# rf24_nano-shield.net
KiCad netlist of a schematic drawn in EAGLE
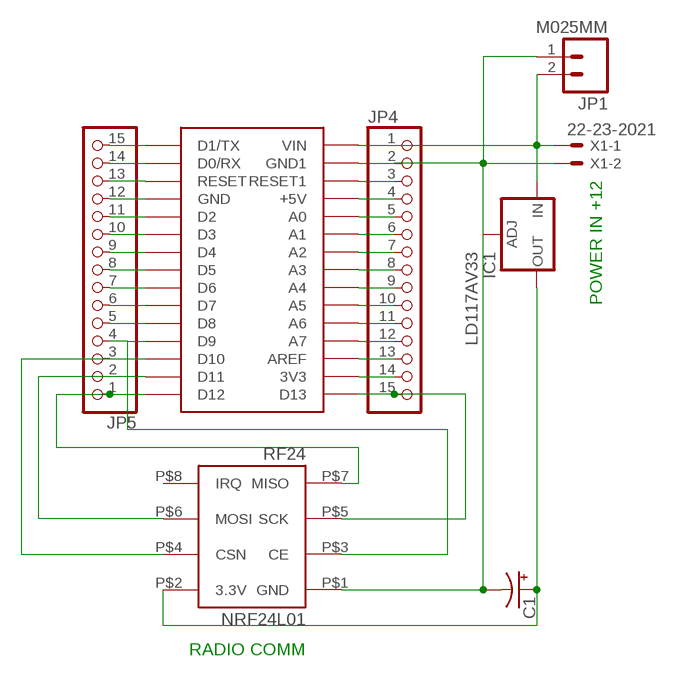
[diagram p0: schematic, sheet 1]

(export (version "E")
  (design (tool "Eeschema 10.0.6"))
  (components
    (comp (ref "C1")
      (value "CPOL-USTT2D5")
      (footprint "eagle-import:TT2D5")
      (libsource (lib "eagle-import") (part "CPOL-USTT2D5"))
    )
    (comp (ref "IC1")
      (value "LD117AV33")
      (footprint "eagle-import:TO220L1")
      (libsource (lib "eagle-import") (part "LD117A?V33"))
    )
    (comp (ref "JP1")
      (value "M025MM")
      (footprint "eagle-import:SCREWTERMINAL-5MM-2")
      (libsource (lib "eagle-import") (part "M025MM"))
    )
    (comp (ref "JP4")
      (value "PINHD-1X15")
      (footprint "eagle-import:1X15")
      (libsource (lib "eagle-import") (part "PINHD-1X15"))
    )
    (comp (ref "JP5")
      (value "PINHD-1X15")
      (footprint "eagle-import:1X15")
      (libsource (lib "eagle-import") (part "PINHD-1X15"))
    )
    (comp (ref "NRF24L01")
      (value "RF24")
      (footprint "eagle-import:4X2HEADER")
      (libsource (lib "eagle-import") (part "RF24"))
    )
    (comp (ref "U$1")
      (value "ARDUINONANO")
      (footprint "eagle-import:PDIP-32")
      (libsource (lib "eagle-import") (part "ARDUINONANO"))
    )
    (comp (ref "X1")
      (value "22-23-2021")
      (footprint "eagle-import:22-23-2021")
      (fields (field (name "MF") "MOLEX"))
      (libsource (lib "eagle-import") (part "22-23-2021"))
    )
  )
  (nets
    (net (code "1") (name "Net-(IC1-ADJ)") (class "Default")
      (node (ref "C1") (pin "-") (pinfunction "-_-") (pintype "passive"))
      (node (ref "IC1") (pin "1") (pinfunction "ADJ_1") (pintype "input"))
      (node (ref "JP1") (pin "1") (pinfunction "1_1") (pintype "passive"))
      (node (ref "JP4") (pin "2") (pinfunction "2_2") (pintype "passive"))
      (node (ref "NRF24L01") (pin "P$1") (pinfunction "GND_P$1") (pintype "bidirectional"))
      (node (ref "U$1") (pin "GND1") (pinfunction "GND1_GND1") (pintype "bidirectional"))
      (node (ref "X1") (pin "2") (pinfunction "S_2") (pintype "passive"))
    )
    (net (code "2") (name "Net-(IC1-IN)") (class "Default")
      (node (ref "IC1") (pin "3") (pinfunction "IN_3") (pintype "input"))
      (node (ref "JP1") (pin "2") (pinfunction "2_2") (pintype "passive"))
      (node (ref "JP4") (pin "1") (pinfunction "1_1") (pintype "passive"))
      (node (ref "U$1") (pin "VIN") (pinfunction "VIN_VIN") (pintype "bidirectional"))
      (node (ref "X1") (pin "1") (pinfunction "S_1") (pintype "passive"))
    )
    (net (code "3") (name "Net-(IC1-OUT)") (class "Default")
      (node (ref "C1") (pin "+") (pinfunction "+_+") (pintype "passive"))
      (node (ref "IC1") (pin "2") (pinfunction "OUT_2") (pintype "passive"))
      (node (ref "NRF24L01") (pin "P$2") (pinfunction "3.3V_P$2") (pintype "bidirectional"))
    )
    (net (code "4") (name "Net-(JP4-Pad3)") (class "Default")
      (node (ref "JP4") (pin "3") (pinfunction "3_3") (pintype "passive"))
      (node (ref "U$1") (pin "RESET1") (pinfunction "RESET1_RESET1") (pintype "bidirectional"))
    )
    (net (code "5") (name "Net-(JP4-Pad4)") (class "Default")
      (node (ref "JP4") (pin "4") (pinfunction "4_4") (pintype "passive"))
      (node (ref "U$1") (pin "+5V") (pinfunction "+5V_+5V") (pintype "bidirectional"))
    )
    (net (code "6") (name "Net-(JP4-Pad5)") (class "Default")
      (node (ref "JP4") (pin "5") (pinfunction "5_5") (pintype "passive"))
      (node (ref "U$1") (pin "A0") (pinfunction "A0_A0") (pintype "bidirectional"))
    )
    (net (code "7") (name "Net-(JP4-Pad6)") (class "Default")
      (node (ref "JP4") (pin "6") (pinfunction "6_6") (pintype "passive"))
      (node (ref "U$1") (pin "A1") (pinfunction "A1_A1") (pintype "bidirectional"))
    )
    (net (code "8") (name "Net-(JP4-Pad7)") (class "Default")
      (node (ref "JP4") (pin "7") (pinfunction "7_7") (pintype "passive"))
      (node (ref "U$1") (pin "A2") (pinfunction "A2_A2") (pintype "bidirectional"))
    )
    (net (code "9") (name "Net-(JP4-Pad8)") (class "Default")
      (node (ref "JP4") (pin "8") (pinfunction "8_8") (pintype "passive"))
      (node (ref "U$1") (pin "A3") (pinfunction "A3_A3") (pintype "bidirectional"))
    )
    (net (code "10") (name "Net-(JP4-Pad9)") (class "Default")
      (node (ref "JP4") (pin "9") (pinfunction "9_9") (pintype "passive"))
      (node (ref "U$1") (pin "A4") (pinfunction "A4_A4") (pintype "bidirectional"))
    )
    (net (code "11") (name "Net-(JP4-Pad10)") (class "Default")
      (node (ref "JP4") (pin "10") (pinfunction "10_10") (pintype "passive"))
      (node (ref "U$1") (pin "A5") (pinfunction "A5_A5") (pintype "bidirectional"))
    )
    (net (code "12") (name "Net-(JP4-Pad11)") (class "Default")
      (node (ref "JP4") (pin "11") (pinfunction "11_11") (pintype "passive"))
      (node (ref "U$1") (pin "A6") (pinfunction "A6_A6") (pintype "bidirectional"))
    )
    (net (code "13") (name "Net-(JP4-Pad12)") (class "Default")
      (node (ref "JP4") (pin "12") (pinfunction "12_12") (pintype "passive"))
      (node (ref "U$1") (pin "A7") (pinfunction "A7_A7") (pintype "bidirectional"))
    )
    (net (code "14") (name "Net-(JP4-Pad13)") (class "Default")
      (node (ref "JP4") (pin "13") (pinfunction "13_13") (pintype "passive"))
      (node (ref "U$1") (pin "AREF") (pinfunction "AREF_AREF") (pintype "bidirectional"))
    )
    (net (code "15") (name "Net-(JP4-Pad14)") (class "Default")
      (node (ref "JP4") (pin "14") (pinfunction "14_14") (pintype "passive"))
      (node (ref "U$1") (pin "3V3") (pinfunction "3V3_3V3") (pintype "bidirectional"))
    )
    (net (code "16") (name "Net-(JP5-Pad5)") (class "Default")
      (node (ref "JP5") (pin "5") (pinfunction "5_5") (pintype "passive"))
      (node (ref "U$1") (pin "D8") (pinfunction "D8_D8") (pintype "bidirectional"))
    )
    (net (code "17") (name "Net-(JP5-Pad6)") (class "Default")
      (node (ref "JP5") (pin "6") (pinfunction "6_6") (pintype "passive"))
      (node (ref "U$1") (pin "D7") (pinfunction "D7_D7") (pintype "bidirectional"))
    )
    (net (code "18") (name "Net-(JP5-Pad7)") (class "Default")
      (node (ref "JP5") (pin "7") (pinfunction "7_7") (pintype "passive"))
      (node (ref "U$1") (pin "D6") (pinfunction "D6_D6") (pintype "bidirectional"))
    )
    (net (code "19") (name "Net-(JP5-Pad8)") (class "Default")
      (node (ref "JP5") (pin "8") (pinfunction "8_8") (pintype "passive"))
      (node (ref "U$1") (pin "D5") (pinfunction "D5_D5") (pintype "bidirectional"))
    )
    (net (code "20") (name "Net-(JP5-Pad9)") (class "Default")
      (node (ref "JP5") (pin "9") (pinfunction "9_9") (pintype "passive"))
      (node (ref "U$1") (pin "D4") (pinfunction "D4_D4") (pintype "bidirectional"))
    )
    (net (code "21") (name "Net-(JP5-Pad10)") (class "Default")
      (node (ref "JP5") (pin "10") (pinfunction "10_10") (pintype "passive"))
      (node (ref "U$1") (pin "D3") (pinfunction "D3_D3") (pintype "bidirectional"))
    )
    (net (code "22") (name "Net-(JP5-Pad11)") (class "Default")
      (node (ref "JP5") (pin "11") (pinfunction "11_11") (pintype "passive"))
      (node (ref "U$1") (pin "D2") (pinfunction "D2_D2") (pintype "bidirectional"))
    )
    (net (code "23") (name "Net-(JP5-Pad12)") (class "Default")
      (node (ref "JP5") (pin "12") (pinfunction "12_12") (pintype "passive"))
      (node (ref "U$1") (pin "GND") (pinfunction "GND_GND") (pintype "bidirectional"))
    )
    (net (code "24") (name "Net-(JP5-Pad13)") (class "Default")
      (node (ref "JP5") (pin "13") (pinfunction "13_13") (pintype "passive"))
      (node (ref "U$1") (pin "RESET") (pinfunction "RESET_RESET") (pintype "bidirectional"))
    )
    (net (code "25") (name "Net-(JP5-Pad14)") (class "Default")
      (node (ref "JP5") (pin "14") (pinfunction "14_14") (pintype "passive"))
      (node (ref "U$1") (pin "D0/RX") (pinfunction "D0/RX_D0/RX") (pintype "bidirectional"))
    )
    (net (code "26") (name "Net-(JP5-Pad15)") (class "Default")
      (node (ref "JP5") (pin "15") (pinfunction "15_15") (pintype "passive"))
      (node (ref "U$1") (pin "D1/TX") (pinfunction "D1/TX_D1/TX") (pintype "bidirectional"))
    )
    (net (code "27") (name "Net-(NRF24L01-CE)") (class "Default")
      (node (ref "JP5") (pin "4") (pinfunction "4_4") (pintype "passive"))
      (node (ref "NRF24L01") (pin "P$3") (pinfunction "CE_P$3") (pintype "bidirectional"))
      (node (ref "U$1") (pin "D9") (pinfunction "D9_D9") (pintype "bidirectional"))
    )
    (net (code "28") (name "Net-(NRF24L01-CSN)") (class "Default")
      (node (ref "NRF24L01") (pin "P$4") (pinfunction "CSN_P$4") (pintype "bidirectional"))
      (node (ref "U$1") (pin "D10") (pinfunction "D10_D10") (pintype "bidirectional"))
    )
    (net (code "29") (name "Net-(NRF24L01-MISO)") (class "Default")
      (node (ref "JP5") (pin "1") (pinfunction "1_1") (pintype "passive"))
      (node (ref "NRF24L01") (pin "P$7") (pinfunction "MISO_P$7") (pintype "bidirectional"))
      (node (ref "U$1") (pin "D12") (pinfunction "D12_D12") (pintype "bidirectional"))
    )
    (net (code "30") (name "Net-(NRF24L01-MOSI)") (class "Default")
      (node (ref "NRF24L01") (pin "P$6") (pinfunction "MOSI_P$6") (pintype "bidirectional"))
      (node (ref "U$1") (pin "D11") (pinfunction "D11_D11") (pintype "bidirectional"))
    )
    (net (code "31") (name "Net-(NRF24L01-SCK)") (class "Default")
      (node (ref "JP4") (pin "15") (pinfunction "15_15") (pintype "passive"))
      (node (ref "NRF24L01") (pin "P$5") (pinfunction "SCK_P$5") (pintype "bidirectional"))
      (node (ref "U$1") (pin "D13") (pinfunction "D13_D13") (pintype "bidirectional"))
    )
    (net (code "32") (name "unconnected-(JP5-Pad2)") (class "Default")
      (node (ref "JP5") (pin "2") (pinfunction "2_2") (pintype "passive"))
    )
    (net (code "33") (name "unconnected-(JP5-Pad3)") (class "Default")
      (node (ref "JP5") (pin "3") (pinfunction "3_3") (pintype "passive"))
    )
    (net (code "34") (name "unconnected-(NRF24L01-IRQ-PadP$8)") (class "Default")
      (node (ref "NRF24L01") (pin "P$8") (pinfunction "IRQ_P$8") (pintype "bidirectional"))
    )
  )
)
